# main.net
KiCad netlist of a schematic drawn in Altium Designer
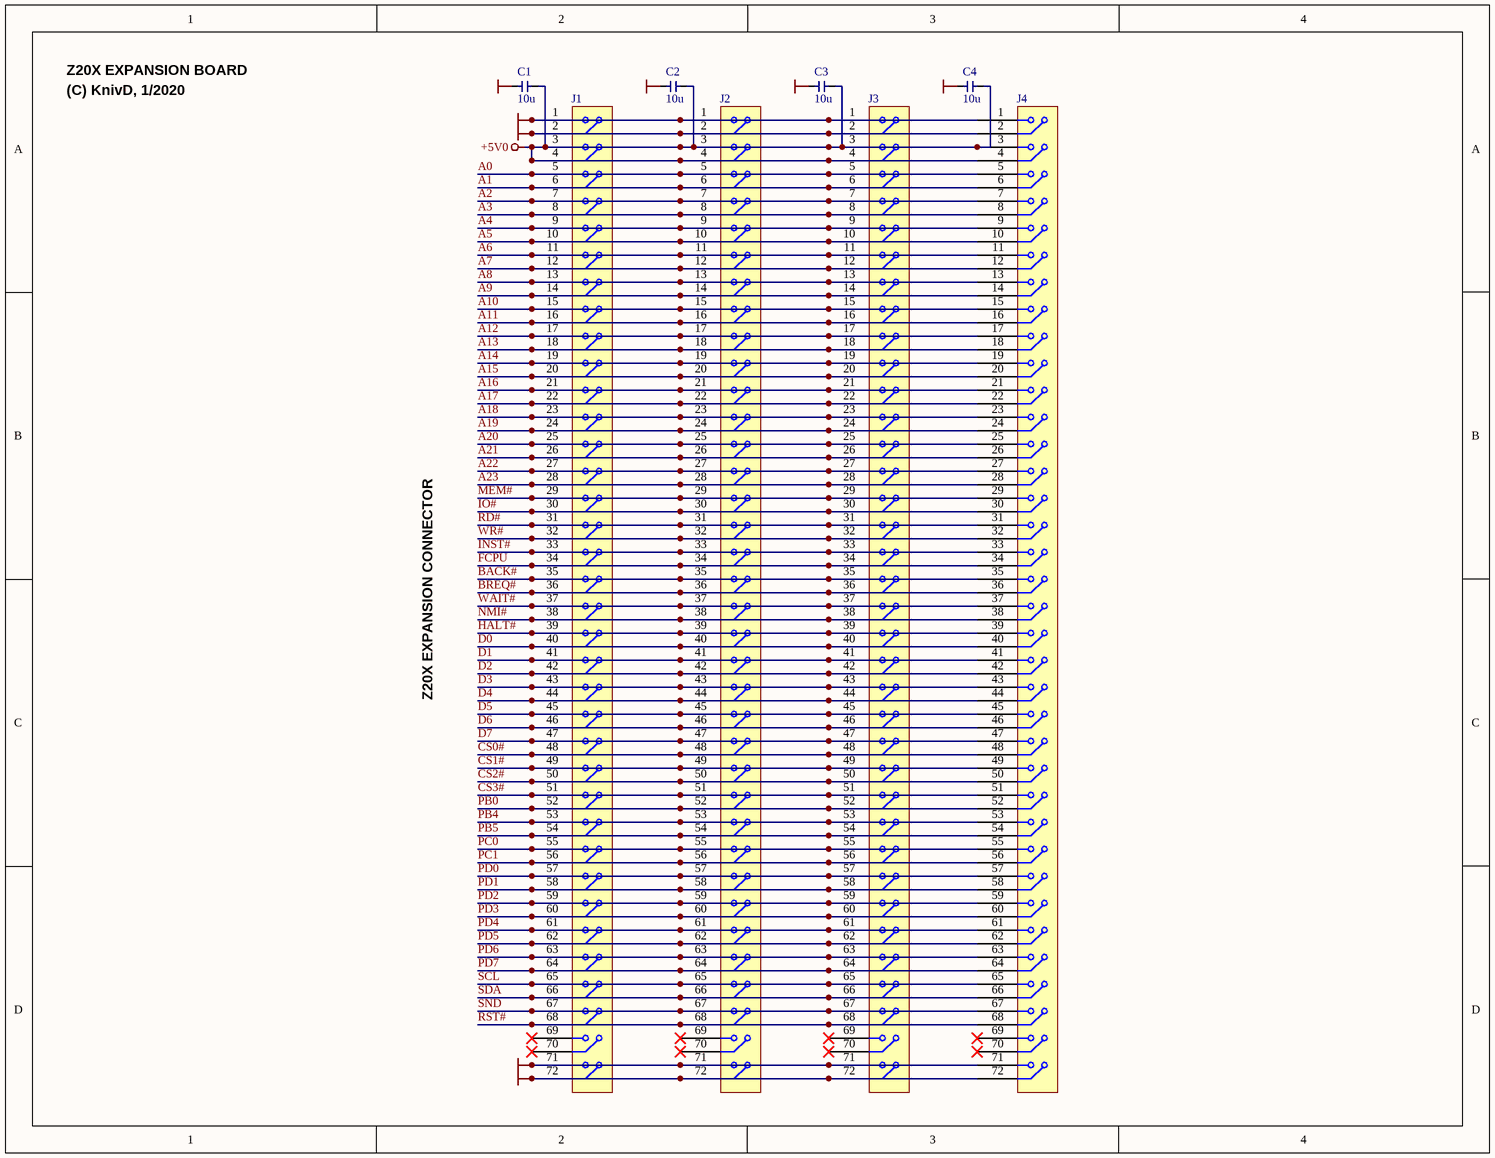
[diagram p0: main.SchDoc]

(export (version "E")
  (design (tool "Eeschema 10.0.6"))
  (components
    (comp (ref "C1")
      (value "10u")
      (footprint "CAPRR508-350X500X500")
      (description "Capacitor")
      (libsource (lib "Discretes") (part "Capacitor"))
    )
    (comp (ref "C2")
      (value "10u")
      (footprint "CAPRR508-350X500X500")
      (description "Capacitor")
      (libsource (lib "Discretes") (part "Capacitor"))
    )
    (comp (ref "C3")
      (value "10u")
      (footprint "CAPRR508-350X500X500")
      (description "Capacitor")
      (libsource (lib "Discretes") (part "Capacitor"))
    )
    (comp (ref "C4")
      (value "10u")
      (footprint "CAPRR508-350X500X500")
      (description "Capacitor")
      (libsource (lib "Discretes") (part "Capacitor"))
    )
    (comp (ref "J1")
      (value "~")
      (footprint "2011-2X36S-F")
      (description "Dual row, 72-way connector")
      (libsource (lib "Connectors") (part "Connector 2x36"))
    )
    (comp (ref "J2")
      (value "~")
      (footprint "2011-2X36S-F")
      (description "Dual row, 72-way connector")
      (libsource (lib "Connectors") (part "Connector 2x36"))
    )
    (comp (ref "J3")
      (value "~")
      (footprint "2011-2X36S-F")
      (description "Dual row, 72-way connector")
      (libsource (lib "Connectors") (part "Connector 2x36"))
    )
    (comp (ref "J4")
      (value "~")
      (footprint "2011-2X36S-F")
      (description "Dual row, 72-way connector")
      (libsource (lib "Connectors") (part "Connector 2x36"))
    )
  )
  (nets
    (net (code "1") (name "+5V0") (class "Default")
      (node (ref "C1") (pin "1") (pintype "passive"))
      (node (ref "C2") (pin "1") (pintype "passive"))
      (node (ref "C3") (pin "1") (pintype "passive"))
      (node (ref "C4") (pin "1") (pintype "passive"))
      (node (ref "J1") (pin "3") (pinfunction "3_3") (pintype "passive"))
      (node (ref "J1") (pin "4") (pinfunction "4_4") (pintype "passive"))
      (node (ref "J2") (pin "3") (pinfunction "3_3") (pintype "passive"))
      (node (ref "J2") (pin "4") (pinfunction "4_4") (pintype "passive"))
      (node (ref "J3") (pin "3") (pinfunction "3_3") (pintype "passive"))
      (node (ref "J3") (pin "4") (pinfunction "4_4") (pintype "passive"))
      (node (ref "J4") (pin "3") (pinfunction "3_3") (pintype "passive"))
      (node (ref "J4") (pin "4") (pinfunction "4_4") (pintype "passive"))
    )
    (net (code "2") (name "/A0") (class "Default")
      (node (ref "J1") (pin "5") (pinfunction "5_5") (pintype "passive"))
      (node (ref "J2") (pin "5") (pinfunction "5_5") (pintype "passive"))
      (node (ref "J3") (pin "5") (pinfunction "5_5") (pintype "passive"))
      (node (ref "J4") (pin "5") (pinfunction "5_5") (pintype "passive"))
    )
    (net (code "3") (name "/A1") (class "Default")
      (node (ref "J1") (pin "6") (pinfunction "6_6") (pintype "passive"))
      (node (ref "J2") (pin "6") (pinfunction "6_6") (pintype "passive"))
      (node (ref "J3") (pin "6") (pinfunction "6_6") (pintype "passive"))
      (node (ref "J4") (pin "6") (pinfunction "6_6") (pintype "passive"))
    )
    (net (code "4") (name "/A2") (class "Default")
      (node (ref "J1") (pin "7") (pinfunction "7_7") (pintype "passive"))
      (node (ref "J2") (pin "7") (pinfunction "7_7") (pintype "passive"))
      (node (ref "J3") (pin "7") (pinfunction "7_7") (pintype "passive"))
      (node (ref "J4") (pin "7") (pinfunction "7_7") (pintype "passive"))
    )
    (net (code "5") (name "/A3") (class "Default")
      (node (ref "J1") (pin "8") (pinfunction "8_8") (pintype "passive"))
      (node (ref "J2") (pin "8") (pinfunction "8_8") (pintype "passive"))
      (node (ref "J3") (pin "8") (pinfunction "8_8") (pintype "passive"))
      (node (ref "J4") (pin "8") (pinfunction "8_8") (pintype "passive"))
    )
    (net (code "6") (name "/A4") (class "Default")
      (node (ref "J1") (pin "9") (pinfunction "9_9") (pintype "passive"))
      (node (ref "J2") (pin "9") (pinfunction "9_9") (pintype "passive"))
      (node (ref "J3") (pin "9") (pinfunction "9_9") (pintype "passive"))
      (node (ref "J4") (pin "9") (pinfunction "9_9") (pintype "passive"))
    )
    (net (code "7") (name "/A5") (class "Default")
      (node (ref "J1") (pin "10") (pinfunction "10_10") (pintype "passive"))
      (node (ref "J2") (pin "10") (pinfunction "10_10") (pintype "passive"))
      (node (ref "J3") (pin "10") (pinfunction "10_10") (pintype "passive"))
      (node (ref "J4") (pin "10") (pinfunction "10_10") (pintype "passive"))
    )
    (net (code "8") (name "/A6") (class "Default")
      (node (ref "J1") (pin "11") (pinfunction "11_11") (pintype "passive"))
      (node (ref "J2") (pin "11") (pinfunction "11_11") (pintype "passive"))
      (node (ref "J3") (pin "11") (pinfunction "11_11") (pintype "passive"))
      (node (ref "J4") (pin "11") (pinfunction "11_11") (pintype "passive"))
    )
    (net (code "9") (name "/A7") (class "Default")
      (node (ref "J1") (pin "12") (pinfunction "12_12") (pintype "passive"))
      (node (ref "J2") (pin "12") (pinfunction "12_12") (pintype "passive"))
      (node (ref "J3") (pin "12") (pinfunction "12_12") (pintype "passive"))
      (node (ref "J4") (pin "12") (pinfunction "12_12") (pintype "passive"))
    )
    (net (code "10") (name "/A8") (class "Default")
      (node (ref "J1") (pin "13") (pinfunction "13_13") (pintype "passive"))
      (node (ref "J2") (pin "13") (pinfunction "13_13") (pintype "passive"))
      (node (ref "J3") (pin "13") (pinfunction "13_13") (pintype "passive"))
      (node (ref "J4") (pin "13") (pinfunction "13_13") (pintype "passive"))
    )
    (net (code "11") (name "/A9") (class "Default")
      (node (ref "J1") (pin "14") (pinfunction "14_14") (pintype "passive"))
      (node (ref "J2") (pin "14") (pinfunction "14_14") (pintype "passive"))
      (node (ref "J3") (pin "14") (pinfunction "14_14") (pintype "passive"))
      (node (ref "J4") (pin "14") (pinfunction "14_14") (pintype "passive"))
    )
    (net (code "12") (name "/A10") (class "Default")
      (node (ref "J1") (pin "15") (pinfunction "15_15") (pintype "passive"))
      (node (ref "J2") (pin "15") (pinfunction "15_15") (pintype "passive"))
      (node (ref "J3") (pin "15") (pinfunction "15_15") (pintype "passive"))
      (node (ref "J4") (pin "15") (pinfunction "15_15") (pintype "passive"))
    )
    (net (code "13") (name "/A11") (class "Default")
      (node (ref "J1") (pin "16") (pinfunction "16_16") (pintype "passive"))
      (node (ref "J2") (pin "16") (pinfunction "16_16") (pintype "passive"))
      (node (ref "J3") (pin "16") (pinfunction "16_16") (pintype "passive"))
      (node (ref "J4") (pin "16") (pinfunction "16_16") (pintype "passive"))
    )
    (net (code "14") (name "/A12") (class "Default")
      (node (ref "J1") (pin "17") (pinfunction "17_17") (pintype "passive"))
      (node (ref "J2") (pin "17") (pinfunction "17_17") (pintype "passive"))
      (node (ref "J3") (pin "17") (pinfunction "17_17") (pintype "passive"))
      (node (ref "J4") (pin "17") (pinfunction "17_17") (pintype "passive"))
    )
    (net (code "15") (name "/A13") (class "Default")
      (node (ref "J1") (pin "18") (pinfunction "18_18") (pintype "passive"))
      (node (ref "J2") (pin "18") (pinfunction "18_18") (pintype "passive"))
      (node (ref "J3") (pin "18") (pinfunction "18_18") (pintype "passive"))
      (node (ref "J4") (pin "18") (pinfunction "18_18") (pintype "passive"))
    )
    (net (code "16") (name "/A14") (class "Default")
      (node (ref "J1") (pin "19") (pinfunction "19_19") (pintype "passive"))
      (node (ref "J2") (pin "19") (pinfunction "19_19") (pintype "passive"))
      (node (ref "J3") (pin "19") (pinfunction "19_19") (pintype "passive"))
      (node (ref "J4") (pin "19") (pinfunction "19_19") (pintype "passive"))
    )
    (net (code "17") (name "/A15") (class "Default")
      (node (ref "J1") (pin "20") (pinfunction "20_20") (pintype "passive"))
      (node (ref "J2") (pin "20") (pinfunction "20_20") (pintype "passive"))
      (node (ref "J3") (pin "20") (pinfunction "20_20") (pintype "passive"))
      (node (ref "J4") (pin "20") (pinfunction "20_20") (pintype "passive"))
    )
    (net (code "18") (name "/A16") (class "Default")
      (node (ref "J1") (pin "21") (pinfunction "21_21") (pintype "passive"))
      (node (ref "J2") (pin "21") (pinfunction "21_21") (pintype "passive"))
      (node (ref "J3") (pin "21") (pinfunction "21_21") (pintype "passive"))
      (node (ref "J4") (pin "21") (pinfunction "21_21") (pintype "passive"))
    )
    (net (code "19") (name "/A17") (class "Default")
      (node (ref "J1") (pin "22") (pinfunction "22_22") (pintype "passive"))
      (node (ref "J2") (pin "22") (pinfunction "22_22") (pintype "passive"))
      (node (ref "J3") (pin "22") (pinfunction "22_22") (pintype "passive"))
      (node (ref "J4") (pin "22") (pinfunction "22_22") (pintype "passive"))
    )
    (net (code "20") (name "/A18") (class "Default")
      (node (ref "J1") (pin "23") (pinfunction "23_23") (pintype "passive"))
      (node (ref "J2") (pin "23") (pinfunction "23_23") (pintype "passive"))
      (node (ref "J3") (pin "23") (pinfunction "23_23") (pintype "passive"))
      (node (ref "J4") (pin "23") (pinfunction "23_23") (pintype "passive"))
    )
    (net (code "21") (name "/A19") (class "Default")
      (node (ref "J1") (pin "24") (pinfunction "24_24") (pintype "passive"))
      (node (ref "J2") (pin "24") (pinfunction "24_24") (pintype "passive"))
      (node (ref "J3") (pin "24") (pinfunction "24_24") (pintype "passive"))
      (node (ref "J4") (pin "24") (pinfunction "24_24") (pintype "passive"))
    )
    (net (code "22") (name "/A20") (class "Default")
      (node (ref "J1") (pin "25") (pinfunction "25_25") (pintype "passive"))
      (node (ref "J2") (pin "25") (pinfunction "25_25") (pintype "passive"))
      (node (ref "J3") (pin "25") (pinfunction "25_25") (pintype "passive"))
      (node (ref "J4") (pin "25") (pinfunction "25_25") (pintype "passive"))
    )
    (net (code "23") (name "/A21") (class "Default")
      (node (ref "J1") (pin "26") (pinfunction "26_26") (pintype "passive"))
      (node (ref "J2") (pin "26") (pinfunction "26_26") (pintype "passive"))
      (node (ref "J3") (pin "26") (pinfunction "26_26") (pintype "passive"))
      (node (ref "J4") (pin "26") (pinfunction "26_26") (pintype "passive"))
    )
    (net (code "24") (name "/A22") (class "Default")
      (node (ref "J1") (pin "27") (pinfunction "27_27") (pintype "passive"))
      (node (ref "J2") (pin "27") (pinfunction "27_27") (pintype "passive"))
      (node (ref "J3") (pin "27") (pinfunction "27_27") (pintype "passive"))
      (node (ref "J4") (pin "27") (pinfunction "27_27") (pintype "passive"))
    )
    (net (code "25") (name "/A23") (class "Default")
      (node (ref "J1") (pin "28") (pinfunction "28_28") (pintype "passive"))
      (node (ref "J2") (pin "28") (pinfunction "28_28") (pintype "passive"))
      (node (ref "J3") (pin "28") (pinfunction "28_28") (pintype "passive"))
      (node (ref "J4") (pin "28") (pinfunction "28_28") (pintype "passive"))
    )
    (net (code "26") (name "/BACK#") (class "Default")
      (node (ref "J1") (pin "35") (pinfunction "35_35") (pintype "passive"))
      (node (ref "J2") (pin "35") (pinfunction "35_35") (pintype "passive"))
      (node (ref "J3") (pin "35") (pinfunction "35_35") (pintype "passive"))
      (node (ref "J4") (pin "35") (pinfunction "35_35") (pintype "passive"))
    )
    (net (code "27") (name "/BREQ#") (class "Default")
      (node (ref "J1") (pin "36") (pinfunction "36_36") (pintype "passive"))
      (node (ref "J2") (pin "36") (pinfunction "36_36") (pintype "passive"))
      (node (ref "J3") (pin "36") (pinfunction "36_36") (pintype "passive"))
      (node (ref "J4") (pin "36") (pinfunction "36_36") (pintype "passive"))
    )
    (net (code "28") (name "/CS0#") (class "Default")
      (node (ref "J1") (pin "48") (pinfunction "48_48") (pintype "passive"))
      (node (ref "J2") (pin "48") (pinfunction "48_48") (pintype "passive"))
      (node (ref "J3") (pin "48") (pinfunction "48_48") (pintype "passive"))
      (node (ref "J4") (pin "48") (pinfunction "48_48") (pintype "passive"))
    )
    (net (code "29") (name "/CS1#") (class "Default")
      (node (ref "J1") (pin "49") (pinfunction "49_49") (pintype "passive"))
      (node (ref "J2") (pin "49") (pinfunction "49_49") (pintype "passive"))
      (node (ref "J3") (pin "49") (pinfunction "49_49") (pintype "passive"))
      (node (ref "J4") (pin "49") (pinfunction "49_49") (pintype "passive"))
    )
    (net (code "30") (name "/CS2#") (class "Default")
      (node (ref "J1") (pin "50") (pinfunction "50_50") (pintype "passive"))
      (node (ref "J2") (pin "50") (pinfunction "50_50") (pintype "passive"))
      (node (ref "J3") (pin "50") (pinfunction "50_50") (pintype "passive"))
      (node (ref "J4") (pin "50") (pinfunction "50_50") (pintype "passive"))
    )
    (net (code "31") (name "/CS3#") (class "Default")
      (node (ref "J1") (pin "51") (pinfunction "51_51") (pintype "passive"))
      (node (ref "J2") (pin "51") (pinfunction "51_51") (pintype "passive"))
      (node (ref "J3") (pin "51") (pinfunction "51_51") (pintype "passive"))
      (node (ref "J4") (pin "51") (pinfunction "51_51") (pintype "passive"))
    )
    (net (code "32") (name "/D0") (class "Default")
      (node (ref "J1") (pin "40") (pinfunction "40_40") (pintype "passive"))
      (node (ref "J2") (pin "40") (pinfunction "40_40") (pintype "passive"))
      (node (ref "J3") (pin "40") (pinfunction "40_40") (pintype "passive"))
      (node (ref "J4") (pin "40") (pinfunction "40_40") (pintype "passive"))
    )
    (net (code "33") (name "/D1") (class "Default")
      (node (ref "J1") (pin "41") (pinfunction "41_41") (pintype "passive"))
      (node (ref "J2") (pin "41") (pinfunction "41_41") (pintype "passive"))
      (node (ref "J3") (pin "41") (pinfunction "41_41") (pintype "passive"))
      (node (ref "J4") (pin "41") (pinfunction "41_41") (pintype "passive"))
    )
    (net (code "34") (name "/D2") (class "Default")
      (node (ref "J1") (pin "42") (pinfunction "42_42") (pintype "passive"))
      (node (ref "J2") (pin "42") (pinfunction "42_42") (pintype "passive"))
      (node (ref "J3") (pin "42") (pinfunction "42_42") (pintype "passive"))
      (node (ref "J4") (pin "42") (pinfunction "42_42") (pintype "passive"))
    )
    (net (code "35") (name "/D3") (class "Default")
      (node (ref "J1") (pin "43") (pinfunction "43_43") (pintype "passive"))
      (node (ref "J2") (pin "43") (pinfunction "43_43") (pintype "passive"))
      (node (ref "J3") (pin "43") (pinfunction "43_43") (pintype "passive"))
      (node (ref "J4") (pin "43") (pinfunction "43_43") (pintype "passive"))
    )
    (net (code "36") (name "/D4") (class "Default")
      (node (ref "J1") (pin "44") (pinfunction "44_44") (pintype "passive"))
      (node (ref "J2") (pin "44") (pinfunction "44_44") (pintype "passive"))
      (node (ref "J3") (pin "44") (pinfunction "44_44") (pintype "passive"))
      (node (ref "J4") (pin "44") (pinfunction "44_44") (pintype "passive"))
    )
    (net (code "37") (name "/D5") (class "Default")
      (node (ref "J1") (pin "45") (pinfunction "45_45") (pintype "passive"))
      (node (ref "J2") (pin "45") (pinfunction "45_45") (pintype "passive"))
      (node (ref "J3") (pin "45") (pinfunction "45_45") (pintype "passive"))
      (node (ref "J4") (pin "45") (pinfunction "45_45") (pintype "passive"))
    )
    (net (code "38") (name "/D6") (class "Default")
      (node (ref "J1") (pin "46") (pinfunction "46_46") (pintype "passive"))
      (node (ref "J2") (pin "46") (pinfunction "46_46") (pintype "passive"))
      (node (ref "J3") (pin "46") (pinfunction "46_46") (pintype "passive"))
      (node (ref "J4") (pin "46") (pinfunction "46_46") (pintype "passive"))
    )
    (net (code "39") (name "/D7") (class "Default")
      (node (ref "J1") (pin "47") (pinfunction "47_47") (pintype "passive"))
      (node (ref "J2") (pin "47") (pinfunction "47_47") (pintype "passive"))
      (node (ref "J3") (pin "47") (pinfunction "47_47") (pintype "passive"))
      (node (ref "J4") (pin "47") (pinfunction "47_47") (pintype "passive"))
    )
    (net (code "40") (name "/FCPU") (class "Default")
      (node (ref "J1") (pin "34") (pinfunction "34_34") (pintype "passive"))
      (node (ref "J2") (pin "34") (pinfunction "34_34") (pintype "passive"))
      (node (ref "J3") (pin "34") (pinfunction "34_34") (pintype "passive"))
      (node (ref "J4") (pin "34") (pinfunction "34_34") (pintype "passive"))
    )
    (net (code "41") (name "/HALT#") (class "Default")
      (node (ref "J1") (pin "39") (pinfunction "39_39") (pintype "passive"))
      (node (ref "J2") (pin "39") (pinfunction "39_39") (pintype "passive"))
      (node (ref "J3") (pin "39") (pinfunction "39_39") (pintype "passive"))
      (node (ref "J4") (pin "39") (pinfunction "39_39") (pintype "passive"))
    )
    (net (code "42") (name "/INST#") (class "Default")
      (node (ref "J1") (pin "33") (pinfunction "33_33") (pintype "passive"))
      (node (ref "J2") (pin "33") (pinfunction "33_33") (pintype "passive"))
      (node (ref "J3") (pin "33") (pinfunction "33_33") (pintype "passive"))
      (node (ref "J4") (pin "33") (pinfunction "33_33") (pintype "passive"))
    )
    (net (code "43") (name "/IO#") (class "Default")
      (node (ref "J1") (pin "30") (pinfunction "30_30") (pintype "passive"))
      (node (ref "J2") (pin "30") (pinfunction "30_30") (pintype "passive"))
      (node (ref "J3") (pin "30") (pinfunction "30_30") (pintype "passive"))
      (node (ref "J4") (pin "30") (pinfunction "30_30") (pintype "passive"))
    )
    (net (code "44") (name "/MEM#") (class "Default")
      (node (ref "J1") (pin "29") (pinfunction "29_29") (pintype "passive"))
      (node (ref "J2") (pin "29") (pinfunction "29_29") (pintype "passive"))
      (node (ref "J3") (pin "29") (pinfunction "29_29") (pintype "passive"))
      (node (ref "J4") (pin "29") (pinfunction "29_29") (pintype "passive"))
    )
    (net (code "45") (name "/NMI#") (class "Default")
      (node (ref "J1") (pin "38") (pinfunction "38_38") (pintype "passive"))
      (node (ref "J2") (pin "38") (pinfunction "38_38") (pintype "passive"))
      (node (ref "J3") (pin "38") (pinfunction "38_38") (pintype "passive"))
      (node (ref "J4") (pin "38") (pinfunction "38_38") (pintype "passive"))
    )
    (net (code "46") (name "/PB0") (class "Default")
      (node (ref "J1") (pin "52") (pinfunction "52_52") (pintype "passive"))
      (node (ref "J2") (pin "52") (pinfunction "52_52") (pintype "passive"))
      (node (ref "J3") (pin "52") (pinfunction "52_52") (pintype "passive"))
      (node (ref "J4") (pin "52") (pinfunction "52_52") (pintype "passive"))
    )
    (net (code "47") (name "/PB4") (class "Default")
      (node (ref "J1") (pin "53") (pinfunction "53_53") (pintype "passive"))
      (node (ref "J2") (pin "53") (pinfunction "53_53") (pintype "passive"))
      (node (ref "J3") (pin "53") (pinfunction "53_53") (pintype "passive"))
      (node (ref "J4") (pin "53") (pinfunction "53_53") (pintype "passive"))
    )
    (net (code "48") (name "/PB5") (class "Default")
      (node (ref "J1") (pin "54") (pinfunction "54_54") (pintype "passive"))
      (node (ref "J2") (pin "54") (pinfunction "54_54") (pintype "passive"))
      (node (ref "J3") (pin "54") (pinfunction "54_54") (pintype "passive"))
      (node (ref "J4") (pin "54") (pinfunction "54_54") (pintype "passive"))
    )
    (net (code "49") (name "/PC0") (class "Default")
      (node (ref "J1") (pin "55") (pinfunction "55_55") (pintype "passive"))
      (node (ref "J2") (pin "55") (pinfunction "55_55") (pintype "passive"))
      (node (ref "J3") (pin "55") (pinfunction "55_55") (pintype "passive"))
      (node (ref "J4") (pin "55") (pinfunction "55_55") (pintype "passive"))
    )
    (net (code "50") (name "/PC1") (class "Default")
      (node (ref "J1") (pin "56") (pinfunction "56_56") (pintype "passive"))
      (node (ref "J2") (pin "56") (pinfunction "56_56") (pintype "passive"))
      (node (ref "J3") (pin "56") (pinfunction "56_56") (pintype "passive"))
      (node (ref "J4") (pin "56") (pinfunction "56_56") (pintype "passive"))
    )
    (net (code "51") (name "/PD0") (class "Default")
      (node (ref "J1") (pin "57") (pinfunction "57_57") (pintype "passive"))
      (node (ref "J2") (pin "57") (pinfunction "57_57") (pintype "passive"))
      (node (ref "J3") (pin "57") (pinfunction "57_57") (pintype "passive"))
      (node (ref "J4") (pin "57") (pinfunction "57_57") (pintype "passive"))
    )
    (net (code "52") (name "/PD1") (class "Default")
      (node (ref "J1") (pin "58") (pinfunction "58_58") (pintype "passive"))
      (node (ref "J2") (pin "58") (pinfunction "58_58") (pintype "passive"))
      (node (ref "J3") (pin "58") (pinfunction "58_58") (pintype "passive"))
      (node (ref "J4") (pin "58") (pinfunction "58_58") (pintype "passive"))
    )
    (net (code "53") (name "/PD2") (class "Default")
      (node (ref "J1") (pin "59") (pinfunction "59_59") (pintype "passive"))
      (node (ref "J2") (pin "59") (pinfunction "59_59") (pintype "passive"))
      (node (ref "J3") (pin "59") (pinfunction "59_59") (pintype "passive"))
      (node (ref "J4") (pin "59") (pinfunction "59_59") (pintype "passive"))
    )
    (net (code "54") (name "/PD3") (class "Default")
      (node (ref "J1") (pin "60") (pinfunction "60_60") (pintype "passive"))
      (node (ref "J2") (pin "60") (pinfunction "60_60") (pintype "passive"))
      (node (ref "J3") (pin "60") (pinfunction "60_60") (pintype "passive"))
      (node (ref "J4") (pin "60") (pinfunction "60_60") (pintype "passive"))
    )
    (net (code "55") (name "/PD4") (class "Default")
      (node (ref "J1") (pin "61") (pinfunction "61_61") (pintype "passive"))
      (node (ref "J2") (pin "61") (pinfunction "61_61") (pintype "passive"))
      (node (ref "J3") (pin "61") (pinfunction "61_61") (pintype "passive"))
      (node (ref "J4") (pin "61") (pinfunction "61_61") (pintype "passive"))
    )
    (net (code "56") (name "/PD5") (class "Default")
      (node (ref "J1") (pin "62") (pinfunction "62_62") (pintype "passive"))
      (node (ref "J2") (pin "62") (pinfunction "62_62") (pintype "passive"))
      (node (ref "J3") (pin "62") (pinfunction "62_62") (pintype "passive"))
      (node (ref "J4") (pin "62") (pinfunction "62_62") (pintype "passive"))
    )
    (net (code "57") (name "/PD6") (class "Default")
      (node (ref "J1") (pin "63") (pinfunction "63_63") (pintype "passive"))
      (node (ref "J2") (pin "63") (pinfunction "63_63") (pintype "passive"))
      (node (ref "J3") (pin "63") (pinfunction "63_63") (pintype "passive"))
      (node (ref "J4") (pin "63") (pinfunction "63_63") (pintype "passive"))
    )
    (net (code "58") (name "/PD7") (class "Default")
      (node (ref "J1") (pin "64") (pinfunction "64_64") (pintype "passive"))
      (node (ref "J2") (pin "64") (pinfunction "64_64") (pintype "passive"))
      (node (ref "J3") (pin "64") (pinfunction "64_64") (pintype "passive"))
      (node (ref "J4") (pin "64") (pinfunction "64_64") (pintype "passive"))
    )
    (net (code "59") (name "/RD#") (class "Default")
      (node (ref "J1") (pin "31") (pinfunction "31_31") (pintype "passive"))
      (node (ref "J2") (pin "31") (pinfunction "31_31") (pintype "passive"))
      (node (ref "J3") (pin "31") (pinfunction "31_31") (pintype "passive"))
      (node (ref "J4") (pin "31") (pinfunction "31_31") (pintype "passive"))
    )
    (net (code "60") (name "/RST#") (class "Default")
      (node (ref "J1") (pin "68") (pinfunction "68_68") (pintype "passive"))
      (node (ref "J2") (pin "68") (pinfunction "68_68") (pintype "passive"))
      (node (ref "J3") (pin "68") (pinfunction "68_68") (pintype "passive"))
      (node (ref "J4") (pin "68") (pinfunction "68_68") (pintype "passive"))
    )
    (net (code "61") (name "/SCL") (class "Default")
      (node (ref "J1") (pin "65") (pinfunction "65_65") (pintype "passive"))
      (node (ref "J2") (pin "65") (pinfunction "65_65") (pintype "passive"))
      (node (ref "J3") (pin "65") (pinfunction "65_65") (pintype "passive"))
      (node (ref "J4") (pin "65") (pinfunction "65_65") (pintype "passive"))
    )
    (net (code "62") (name "/SDA") (class "Default")
      (node (ref "J1") (pin "66") (pinfunction "66_66") (pintype "passive"))
      (node (ref "J2") (pin "66") (pinfunction "66_66") (pintype "passive"))
      (node (ref "J3") (pin "66") (pinfunction "66_66") (pintype "passive"))
      (node (ref "J4") (pin "66") (pinfunction "66_66") (pintype "passive"))
    )
    (net (code "63") (name "/SND") (class "Default")
      (node (ref "J1") (pin "67") (pinfunction "67_67") (pintype "passive"))
      (node (ref "J2") (pin "67") (pinfunction "67_67") (pintype "passive"))
      (node (ref "J3") (pin "67") (pinfunction "67_67") (pintype "passive"))
      (node (ref "J4") (pin "67") (pinfunction "67_67") (pintype "passive"))
    )
    (net (code "64") (name "/WAIT#") (class "Default")
      (node (ref "J1") (pin "37") (pinfunction "37_37") (pintype "passive"))
      (node (ref "J2") (pin "37") (pinfunction "37_37") (pintype "passive"))
      (node (ref "J3") (pin "37") (pinfunction "37_37") (pintype "passive"))
      (node (ref "J4") (pin "37") (pinfunction "37_37") (pintype "passive"))
    )
    (net (code "65") (name "/WR#") (class "Default")
      (node (ref "J1") (pin "32") (pinfunction "32_32") (pintype "passive"))
      (node (ref "J2") (pin "32") (pinfunction "32_32") (pintype "passive"))
      (node (ref "J3") (pin "32") (pinfunction "32_32") (pintype "passive"))
      (node (ref "J4") (pin "32") (pinfunction "32_32") (pintype "passive"))
    )
    (net (code "66") (name "GND") (class "Default")
      (node (ref "C1") (pin "2") (pintype "passive"))
      (node (ref "C2") (pin "2") (pintype "passive"))
      (node (ref "C3") (pin "2") (pintype "passive"))
      (node (ref "C4") (pin "2") (pintype "passive"))
      (node (ref "J1") (pin "1") (pinfunction "1_1") (pintype "passive"))
      (node (ref "J1") (pin "2") (pinfunction "2_2") (pintype "passive"))
      (node (ref "J1") (pin "71") (pinfunction "71_71") (pintype "passive"))
      (node (ref "J1") (pin "72") (pinfunction "72_72") (pintype "passive"))
      (node (ref "J2") (pin "1") (pinfunction "1_1") (pintype "passive"))
      (node (ref "J2") (pin "2") (pinfunction "2_2") (pintype "passive"))
      (node (ref "J2") (pin "71") (pinfunction "71_71") (pintype "passive"))
      (node (ref "J2") (pin "72") (pinfunction "72_72") (pintype "passive"))
      (node (ref "J3") (pin "1") (pinfunction "1_1") (pintype "passive"))
      (node (ref "J3") (pin "2") (pinfunction "2_2") (pintype "passive"))
      (node (ref "J3") (pin "71") (pinfunction "71_71") (pintype "passive"))
      (node (ref "J3") (pin "72") (pinfunction "72_72") (pintype "passive"))
      (node (ref "J4") (pin "1") (pinfunction "1_1") (pintype "passive"))
      (node (ref "J4") (pin "2") (pinfunction "2_2") (pintype "passive"))
      (node (ref "J4") (pin "71") (pinfunction "71_71") (pintype "passive"))
      (node (ref "J4") (pin "72") (pinfunction "72_72") (pintype "passive"))
    )
    (net (code "67") (name "unconnected-(J1-Pad69)") (class "Default")
      (node (ref "J1") (pin "69") (pinfunction "69_69") (pintype "passive+no_connect"))
    )
    (net (code "68") (name "unconnected-(J1-Pad70)") (class "Default")
      (node (ref "J1") (pin "70") (pinfunction "70_70") (pintype "passive+no_connect"))
    )
    (net (code "69") (name "unconnected-(J2-Pad69)") (class "Default")
      (node (ref "J2") (pin "69") (pinfunction "69_69") (pintype "passive+no_connect"))
    )
    (net (code "70") (name "unconnected-(J2-Pad70)") (class "Default")
      (node (ref "J2") (pin "70") (pinfunction "70_70") (pintype "passive+no_connect"))
    )
    (net (code "71") (name "unconnected-(J3-Pad69)") (class "Default")
      (node (ref "J3") (pin "69") (pinfunction "69_69") (pintype "passive+no_connect"))
    )
    (net (code "72") (name "unconnected-(J3-Pad70)") (class "Default")
      (node (ref "J3") (pin "70") (pinfunction "70_70") (pintype "passive+no_connect"))
    )
    (net (code "73") (name "unconnected-(J4-Pad69)") (class "Default")
      (node (ref "J4") (pin "69") (pinfunction "69_69") (pintype "passive+no_connect"))
    )
    (net (code "74") (name "unconnected-(J4-Pad70)") (class "Default")
      (node (ref "J4") (pin "70") (pinfunction "70_70") (pintype "passive+no_connect"))
    )
  )
)
